# CMoy-Pro-V_1_0_0_2a.net
KiCad netlist of a schematic drawn in EAGLE
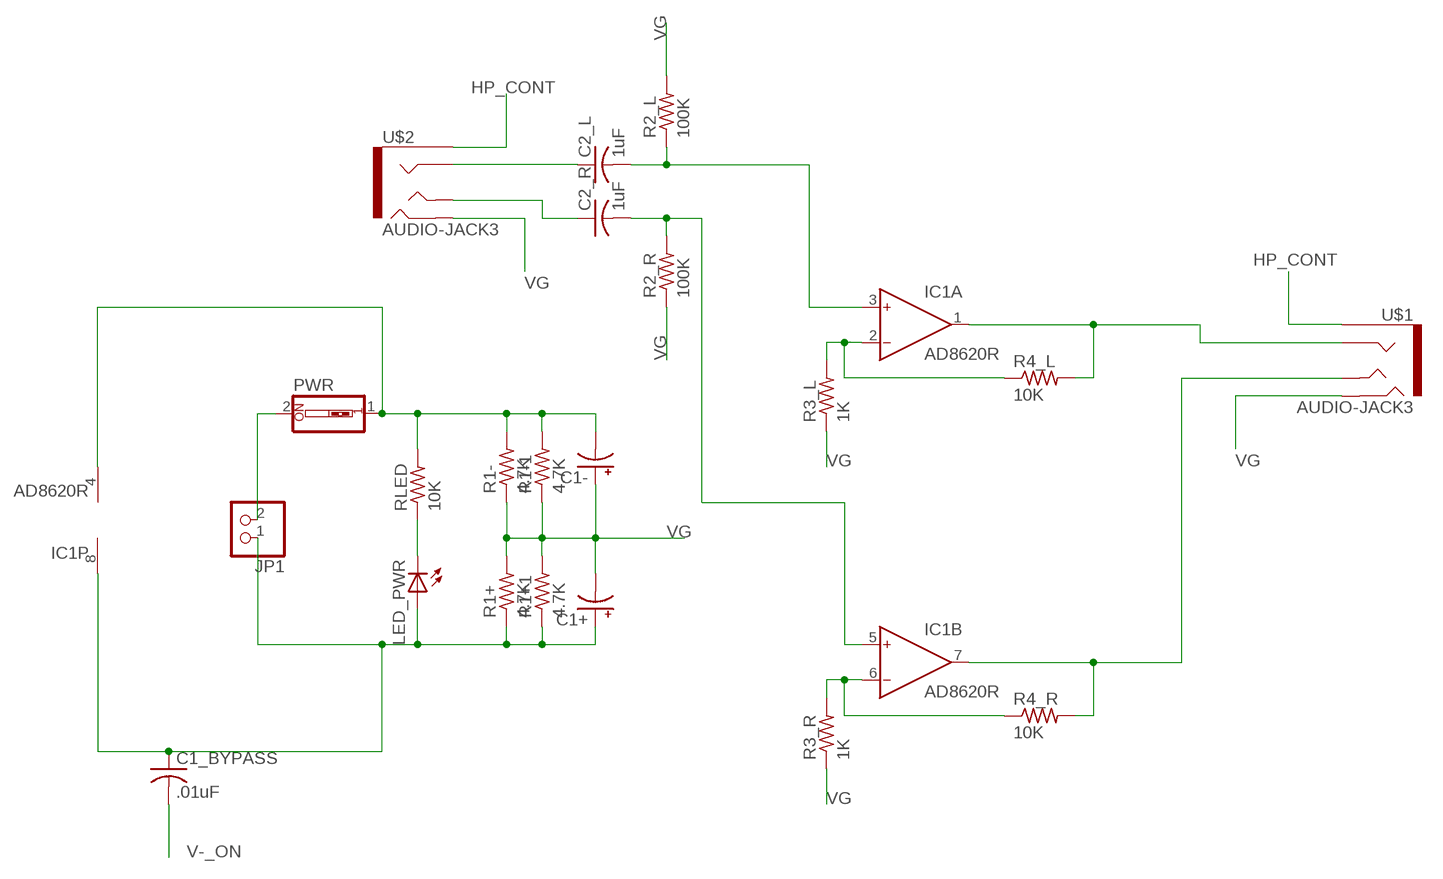
[diagram p0: schematic, sheet 1]

(export (version "E")
  (design (tool "Eeschema 10.0.6"))
  (components
    (comp (ref "C1+")
      (value "CPOL-US140CLH-0810")
      (footprint "eagle-import:140CLH-0810")
      (libsource (lib "eagle-import") (part "CPOL-US140CLH-0810"))
    )
    (comp (ref "C1-")
      (value "CPOL-US140CLH-0810")
      (footprint "eagle-import:140CLH-0810")
      (libsource (lib "eagle-import") (part "CPOL-US140CLH-0810"))
    )
    (comp (ref "C1_BYPASS")
      (value ".01uF")
      (footprint "eagle-import:C0603")
      (libsource (lib "eagle-import") (part "C-USC0603"))
    )
    (comp (ref "C2_L")
      (value "1uF")
      (footprint "eagle-import:C1210")
      (libsource (lib "eagle-import") (part "C-USC1210"))
    )
    (comp (ref "C2_R")
      (value "1uF")
      (footprint "eagle-import:C1210")
      (libsource (lib "eagle-import") (part "C-USC1210"))
    )
    (comp (ref "IC1")
      (value "AD8620R")
      (footprint "eagle-import:SO8")
      (fields (field (name "MF") "ALTERA CORPORATION") (field (name "MPN") "AD8620ARZ"))
      (libsource (lib "eagle-import") (part "AD8620R"))
    )
    (comp (ref "JP1")
      (value "PINHD-1X2")
      (footprint "eagle-import:1X02")
      (libsource (lib "eagle-import") (part "PINHD-1X2"))
    )
    (comp (ref "LED_PWR")
      (value "LEDCHIP-LED0603")
      (footprint "eagle-import:CHIP-LED0603")
      (libsource (lib "eagle-import") (part "LEDCHIP-LED0603"))
    )
    (comp (ref "PWR")
      (value "SW_DIP-1")
      (footprint "eagle-import:EDG-01")
      (libsource (lib "eagle-import") (part "SW_DIP-1"))
    )
    (comp (ref "R1+")
      (value "4.7K")
      (footprint "eagle-import:R0603")
      (libsource (lib "eagle-import") (part "R-US_R0603"))
    )
    (comp (ref "R1+1")
      (value "4.7K")
      (footprint "eagle-import:R0603")
      (libsource (lib "eagle-import") (part "R-US_R0603"))
    )
    (comp (ref "R1-")
      (value "4.7K")
      (footprint "eagle-import:R0603")
      (libsource (lib "eagle-import") (part "R-US_R0603"))
    )
    (comp (ref "R1-1")
      (value "4.7K")
      (footprint "eagle-import:R0603")
      (libsource (lib "eagle-import") (part "R-US_R0603"))
    )
    (comp (ref "R2_L")
      (value "100K")
      (footprint "eagle-import:R0603")
      (libsource (lib "eagle-import") (part "R-US_R0603"))
    )
    (comp (ref "R2_R")
      (value "100K")
      (footprint "eagle-import:R0603")
      (libsource (lib "eagle-import") (part "R-US_R0603"))
    )
    (comp (ref "R3_L")
      (value "1K")
      (footprint "eagle-import:R0603")
      (libsource (lib "eagle-import") (part "R-US_R0603"))
    )
    (comp (ref "R3_R")
      (value "1K")
      (footprint "eagle-import:R0603")
      (libsource (lib "eagle-import") (part "R-US_R0603"))
    )
    (comp (ref "R4_L")
      (value "10K")
      (footprint "eagle-import:R0603")
      (libsource (lib "eagle-import") (part "R-US_R0603"))
    )
    (comp (ref "R4_R")
      (value "10K")
      (footprint "eagle-import:R0603")
      (libsource (lib "eagle-import") (part "R-US_R0603"))
    )
    (comp (ref "RLED")
      (value "10K")
      (footprint "eagle-import:R0603")
      (libsource (lib "eagle-import") (part "R-US_R0603"))
    )
    (comp (ref "U$1")
      (value "AUDIO-JACK3")
      (footprint "eagle-import:AUDIO-JACK-TRRS-SMD")
      (libsource (lib "eagle-import") (part "AUDIO-JACK3"))
    )
    (comp (ref "U$2")
      (value "AUDIO-JACK3")
      (footprint "eagle-import:AUDIO-JACK-TRRS-SMD")
      (libsource (lib "eagle-import") (part "AUDIO-JACK3"))
    )
  )
  (nets
    (net (code "1") (name "/HP_CONT") (class "Default")
      (node (ref "U$1") (pin "EARTH") (pinfunction "EARTH_EARTH") (pintype "bidirectional"))
      (node (ref "U$2") (pin "EARTH") (pinfunction "EARTH_EARTH") (pintype "bidirectional"))
    )
    (net (code "2") (name "/V-_ON") (class "Default")
      (node (ref "C1-") (pin "-") (pinfunction "-_-") (pintype "passive"))
      (node (ref "C1_BYPASS") (pin "2") (pinfunction "2_2") (pintype "passive"))
      (node (ref "IC1") (pin "4") (pinfunction "V-_4") (pintype "power_in"))
      (node (ref "PWR") (pin "1") (pinfunction "1_1") (pintype "passive"))
      (node (ref "R1-") (pin "2") (pinfunction "2_2") (pintype "passive"))
      (node (ref "R1-1") (pin "2") (pinfunction "2_2") (pintype "passive"))
      (node (ref "RLED") (pin "2") (pinfunction "2_2") (pintype "passive"))
    )
    (net (code "3") (name "/VG") (class "Default")
      (node (ref "C1+") (pin "-") (pinfunction "-_-") (pintype "passive"))
      (node (ref "C1-") (pin "+") (pinfunction "+_+") (pintype "passive"))
      (node (ref "R1+") (pin "2") (pinfunction "2_2") (pintype "passive"))
      (node (ref "R1+1") (pin "2") (pinfunction "2_2") (pintype "passive"))
      (node (ref "R1-") (pin "1") (pinfunction "1_1") (pintype "passive"))
      (node (ref "R1-1") (pin "1") (pinfunction "1_1") (pintype "passive"))
      (node (ref "R2_L") (pin "2") (pinfunction "2_2") (pintype "passive"))
      (node (ref "R2_R") (pin "1") (pinfunction "1_1") (pintype "passive"))
      (node (ref "R3_L") (pin "1") (pinfunction "1_1") (pintype "passive"))
      (node (ref "R3_R") (pin "1") (pinfunction "1_1") (pintype "passive"))
      (node (ref "U$1") (pin "RING2") (pinfunction "RING2_RING2") (pintype "bidirectional"))
      (node (ref "U$2") (pin "RING2") (pinfunction "RING2_RING2") (pintype "bidirectional"))
    )
    (net (code "4") (name "Net-(C2_L-Pad1)") (class "Default")
      (node (ref "C2_L") (pin "1") (pinfunction "1_1") (pintype "passive"))
      (node (ref "U$2") (pin "RING1") (pinfunction "RING1_RING1") (pintype "bidirectional"))
    )
    (net (code "5") (name "Net-(C2_R-Pad1)") (class "Default")
      (node (ref "C2_R") (pin "1") (pinfunction "1_1") (pintype "passive"))
      (node (ref "U$2") (pin "TIP") (pinfunction "TIP_TIP") (pintype "bidirectional"))
    )
    (net (code "6") (name "Net-(IC1A-IN+)") (class "Default")
      (node (ref "C2_L") (pin "2") (pinfunction "2_2") (pintype "passive"))
      (node (ref "IC1") (pin "3") (pinfunction "IN+_3") (pintype "input"))
      (node (ref "R2_L") (pin "1") (pinfunction "1_1") (pintype "passive"))
    )
    (net (code "7") (name "Net-(IC1A-IN-)") (class "Default")
      (node (ref "IC1") (pin "2") (pinfunction "IN-_2") (pintype "input"))
      (node (ref "R3_L") (pin "2") (pinfunction "2_2") (pintype "passive"))
      (node (ref "R4_L") (pin "1") (pinfunction "1_1") (pintype "passive"))
    )
    (net (code "8") (name "Net-(IC1A-OUT)") (class "Default")
      (node (ref "IC1") (pin "1") (pinfunction "OUT_1") (pintype "output"))
      (node (ref "R4_L") (pin "2") (pinfunction "2_2") (pintype "passive"))
      (node (ref "U$1") (pin "RING1") (pinfunction "RING1_RING1") (pintype "bidirectional"))
    )
    (net (code "9") (name "Net-(IC1B-IN+)") (class "Default")
      (node (ref "C2_R") (pin "2") (pinfunction "2_2") (pintype "passive"))
      (node (ref "IC1") (pin "5") (pinfunction "IN+_5") (pintype "input"))
      (node (ref "R2_R") (pin "2") (pinfunction "2_2") (pintype "passive"))
    )
    (net (code "10") (name "Net-(IC1B-IN-)") (class "Default")
      (node (ref "IC1") (pin "6") (pinfunction "IN-_6") (pintype "input"))
      (node (ref "R3_R") (pin "2") (pinfunction "2_2") (pintype "passive"))
      (node (ref "R4_R") (pin "1") (pinfunction "1_1") (pintype "passive"))
    )
    (net (code "11") (name "Net-(IC1B-OUT)") (class "Default")
      (node (ref "IC1") (pin "7") (pinfunction "OUT_7") (pintype "output"))
      (node (ref "R4_R") (pin "2") (pinfunction "2_2") (pintype "passive"))
      (node (ref "U$1") (pin "TIP") (pinfunction "TIP_TIP") (pintype "bidirectional"))
    )
    (net (code "12") (name "Net-(IC1C-V+)") (class "Default")
      (node (ref "C1+") (pin "+") (pinfunction "+_+") (pintype "passive"))
      (node (ref "C1_BYPASS") (pin "1") (pinfunction "1_1") (pintype "passive"))
      (node (ref "IC1") (pin "8") (pinfunction "V+_8") (pintype "power_in"))
      (node (ref "JP1") (pin "1") (pinfunction "1_1") (pintype "passive"))
      (node (ref "LED_PWR") (pin "A") (pinfunction "A_A") (pintype "passive"))
      (node (ref "R1+") (pin "1") (pinfunction "1_1") (pintype "passive"))
      (node (ref "R1+1") (pin "1") (pinfunction "1_1") (pintype "passive"))
    )
    (net (code "13") (name "Net-(JP1-Pad2)") (class "Default")
      (node (ref "JP1") (pin "2") (pinfunction "2_2") (pintype "passive"))
      (node (ref "PWR") (pin "2") (pinfunction "2_2") (pintype "passive"))
    )
    (net (code "14") (name "Net-(LED_PWR-PadC)") (class "Default")
      (node (ref "LED_PWR") (pin "C") (pinfunction "C_C") (pintype "passive"))
      (node (ref "RLED") (pin "1") (pinfunction "1_1") (pintype "passive"))
    )
  )
)
